# Tag_Tracker_v1.net
KiCad netlist of a schematic drawn in EAGLE
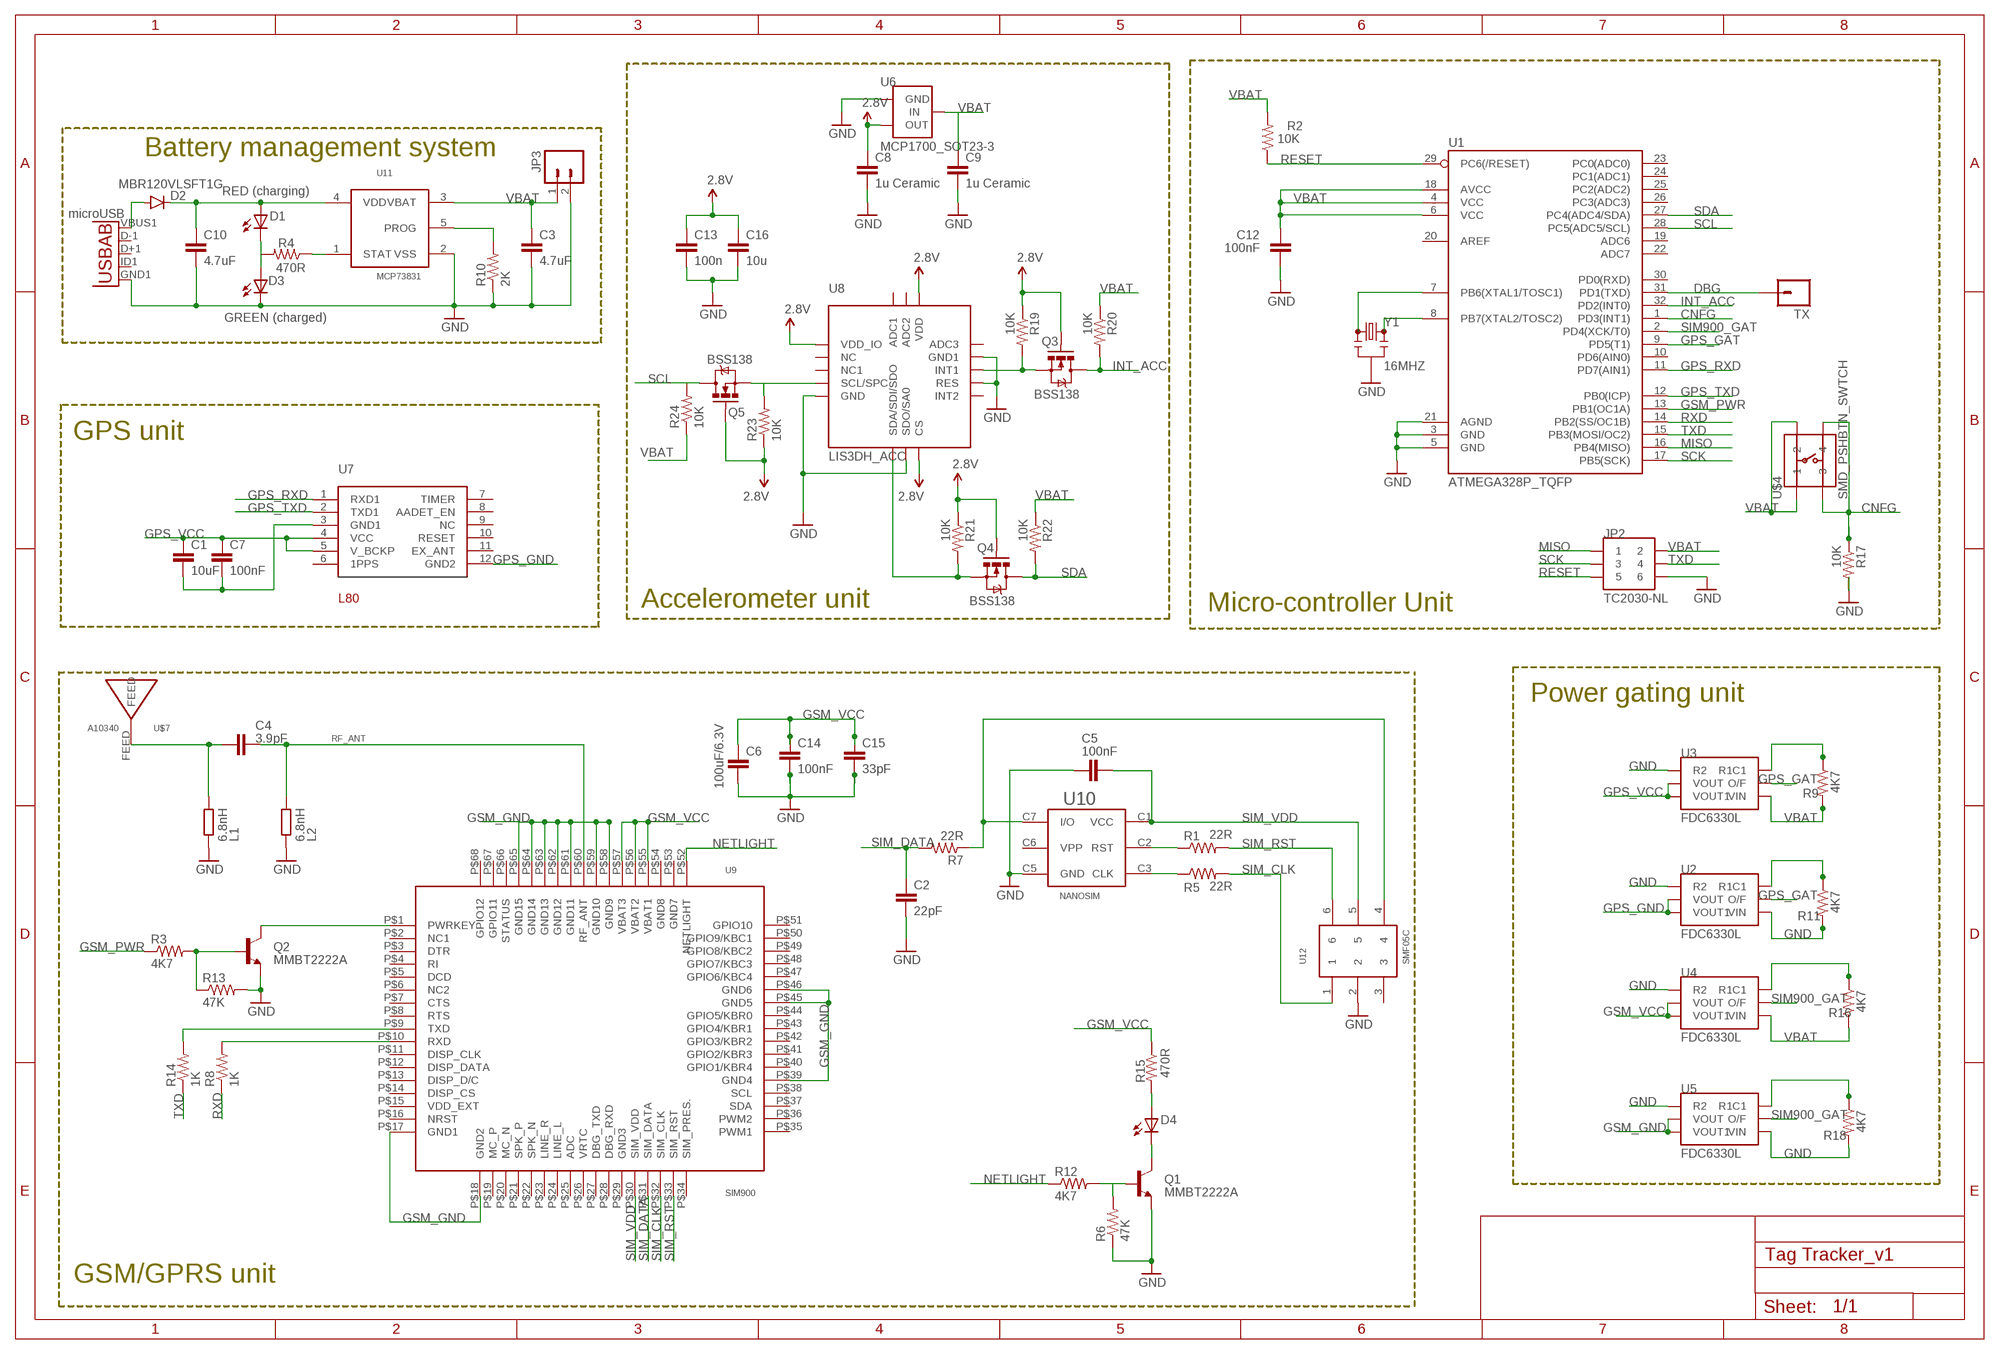
[diagram p0: schematic, sheet 1]

(export (version "E")
  (design (tool "Eeschema 10.0.6"))
  (components
    (comp (ref "C1")
      (value "10uF")
      (footprint "eagle-import:0603-CAP")
      (libsource (lib "eagle-import") (part "CAP0603-CAP"))
    )
    (comp (ref "C2")
      (value "22pF")
      (footprint "eagle-import:0603-CAP")
      (libsource (lib "eagle-import") (part "CAP0603-CAP"))
    )
    (comp (ref "C3")
      (value "4.7uF")
      (footprint "eagle-import:0603-CAP")
      (libsource (lib "eagle-import") (part "CAP0603-CAP"))
    )
    (comp (ref "C4")
      (value "3.9pF")
      (footprint "eagle-import:C0603-ROUND")
      (libsource (lib "eagle-import") (part "C-EU0603-RND"))
    )
    (comp (ref "C5")
      (value "100nF")
      (footprint "eagle-import:0603-CAP")
      (libsource (lib "eagle-import") (part "CAP0603-CAP"))
    )
    (comp (ref "C6")
      (value "100uF/6.3V")
      (footprint "eagle-import:1206")
      (libsource (lib "eagle-import") (part "CAP1206"))
    )
    (comp (ref "C7")
      (value "100nF")
      (footprint "eagle-import:0603-CAP")
      (libsource (lib "eagle-import") (part "CAP0603-CAP"))
    )
    (comp (ref "C8")
      (value "1u Ceramic")
      (footprint "eagle-import:0603-CAP")
      (libsource (lib "eagle-import") (part "0.1UF-100V-10%(0603)"))
    )
    (comp (ref "C9")
      (value "1u Ceramic")
      (footprint "eagle-import:0603-CAP")
      (libsource (lib "eagle-import") (part "0.1UF-100V-10%(0603)"))
    )
    (comp (ref "C10")
      (value "4.7uF")
      (footprint "eagle-import:0603-CAP")
      (libsource (lib "eagle-import") (part "CAP0603-CAP"))
    )
    (comp (ref "C12")
      (value "100nF")
      (footprint "eagle-import:0603-CAP")
      (libsource (lib "eagle-import") (part "CAP0603-CAP"))
    )
    (comp (ref "C13")
      (value "100n")
      (footprint "eagle-import:0603-CAP")
      (libsource (lib "eagle-import") (part "0.1UF-100V-10%(0603)"))
    )
    (comp (ref "C14")
      (value "100nF")
      (footprint "eagle-import:0603-CAP")
      (libsource (lib "eagle-import") (part "CAP0603-CAP"))
    )
    (comp (ref "C15")
      (value "33pF")
      (footprint "eagle-import:0603-CAP")
      (libsource (lib "eagle-import") (part "CAP0603-CAP"))
    )
    (comp (ref "C16")
      (value "10u")
      (footprint "eagle-import:0603-CAP")
      (libsource (lib "eagle-import") (part "0.1UF-100V-10%(0603)"))
    )
    (comp (ref "D1")
      (value "RED (charging)")
      (footprint "eagle-import:SML0603")
      (libsource (lib "eagle-import") (part "LEDSML0603"))
    )
    (comp (ref "D2")
      (value "MBR120VLSFT1G")
      (footprint "eagle-import:SOD-123")
      (libsource (lib "eagle-import") (part "DIODESOD123"))
    )
    (comp (ref "D3")
      (value "GREEN (charged)")
      (footprint "eagle-import:SML0603")
      (libsource (lib "eagle-import") (part "LEDSML0603"))
    )
    (comp (ref "D4")
      (value "LEDSML0603")
      (footprint "eagle-import:SML0603")
      (libsource (lib "eagle-import") (part "LEDSML0603"))
    )
    (comp (ref "JP2")
      (value "TC2030-NL")
      (footprint "eagle-import:TC2030-NL")
      (libsource (lib "eagle-import") (part "TC2030-NL"))
    )
    (comp (ref "JP3")
      (value "M02PTH")
      (footprint "eagle-import:1X02")
      (libsource (lib "eagle-import") (part "M02PTH"))
    )
    (comp (ref "L1")
      (value "6.8nH")
      (footprint "eagle-import:R0603-ROUND")
      (libsource (lib "eagle-import") (part "R-EU_0603-RND"))
    )
    (comp (ref "L2")
      (value "6.8nH")
      (footprint "eagle-import:R0603-ROUND")
      (libsource (lib "eagle-import") (part "R-EU_0603-RND"))
    )
    (comp (ref "MICRO_USB")
      (value "Micro USB")
      (footprint "eagle-import:USB-AB-MICRO-SMD_V03")
      (libsource (lib "eagle-import") (part "USB-ABCONN-11794"))
    )
    (comp (ref "Q1")
      (value "MMBT2222A")
      (footprint "eagle-import:SOT23-3")
      (libsource (lib "eagle-import") (part "TRANSISTOR_NPNMMBT2222A"))
    )
    (comp (ref "Q2")
      (value "MMBT2222A")
      (footprint "eagle-import:SOT23-3")
      (libsource (lib "eagle-import") (part "TRANSISTOR_NPNMMBT2222A"))
    )
    (comp (ref "Q3")
      (value "BSS138")
      (footprint "eagle-import:SOT23-3")
      (libsource (lib "eagle-import") (part "MOSFET-NCHANNELSMD"))
    )
    (comp (ref "Q4")
      (value "BSS138")
      (footprint "eagle-import:SOT23-3")
      (libsource (lib "eagle-import") (part "MOSFET-NCHANNELSMD"))
    )
    (comp (ref "Q5")
      (value "BSS138")
      (footprint "eagle-import:SOT23-3")
      (libsource (lib "eagle-import") (part "MOSFET-NCHANNELSMD"))
    )
    (comp (ref "R1")
      (value "22R")
      (footprint "eagle-import:0603-RES")
      (libsource (lib "eagle-import") (part "SparkFun-Resistors_RESISTOR0603-RES"))
    )
    (comp (ref "R2")
      (value "10K")
      (footprint "eagle-import:0603-RES")
      (libsource (lib "eagle-import") (part "SparkFun-Resistors_RESISTOR0603-RES"))
    )
    (comp (ref "R3")
      (value "4K7")
      (footprint "eagle-import:0603-RES")
      (libsource (lib "eagle-import") (part "SparkFun-Resistors_RESISTOR0603-RES"))
    )
    (comp (ref "R4")
      (value "470R")
      (footprint "eagle-import:0603-RES")
      (libsource (lib "eagle-import") (part "SparkFun-Resistors_RESISTOR0603-RES"))
    )
    (comp (ref "R5")
      (value "22R")
      (footprint "eagle-import:0603-RES")
      (libsource (lib "eagle-import") (part "SparkFun-Resistors_RESISTOR0603-RES"))
    )
    (comp (ref "R6")
      (value "47K")
      (footprint "eagle-import:0603-RES")
      (libsource (lib "eagle-import") (part "SparkFun-Resistors_RESISTOR0603-RES"))
    )
    (comp (ref "R7")
      (value "22R")
      (footprint "eagle-import:0603-RES")
      (libsource (lib "eagle-import") (part "SparkFun-Resistors_RESISTOR0603-RES"))
    )
    (comp (ref "R8")
      (value "1K")
      (footprint "eagle-import:0603-RES")
      (libsource (lib "eagle-import") (part "SparkFun-Resistors_RESISTOR0603-RES"))
    )
    (comp (ref "R9")
      (value "4K7")
      (footprint "eagle-import:0603-RES")
      (libsource (lib "eagle-import") (part "SparkFun-Resistors_RESISTOR0603-RES"))
    )
    (comp (ref "R10")
      (value "2K")
      (footprint "eagle-import:0603-RES")
      (libsource (lib "eagle-import") (part "SparkFun-Resistors_RESISTOR0603-RES"))
    )
    (comp (ref "R11")
      (value "4K7")
      (footprint "eagle-import:0603-RES")
      (libsource (lib "eagle-import") (part "SparkFun-Resistors_RESISTOR0603-RES"))
    )
    (comp (ref "R12")
      (value "4K7")
      (footprint "eagle-import:0603-RES")
      (libsource (lib "eagle-import") (part "SparkFun-Resistors_RESISTOR0603-RES"))
    )
    (comp (ref "R13")
      (value "47K")
      (footprint "eagle-import:0603-RES")
      (libsource (lib "eagle-import") (part "SparkFun-Resistors_RESISTOR0603-RES"))
    )
    (comp (ref "R14")
      (value "1K")
      (footprint "eagle-import:0603-RES")
      (libsource (lib "eagle-import") (part "SparkFun-Resistors_RESISTOR0603-RES"))
    )
    (comp (ref "R15")
      (value "470R")
      (footprint "eagle-import:0603-RES")
      (libsource (lib "eagle-import") (part "SparkFun-Resistors_RESISTOR0603-RES"))
    )
    (comp (ref "R16")
      (value "4K7")
      (footprint "eagle-import:0603-RES")
      (libsource (lib "eagle-import") (part "SparkFun-Resistors_RESISTOR0603-RES"))
    )
    (comp (ref "R17")
      (value "10K")
      (footprint "eagle-import:0603-RES")
      (libsource (lib "eagle-import") (part "SparkFun-Resistors_RESISTOR0603-RES"))
    )
    (comp (ref "R18")
      (value "4K7")
      (footprint "eagle-import:0603-RES")
      (libsource (lib "eagle-import") (part "SparkFun-Resistors_RESISTOR0603-RES"))
    )
    (comp (ref "R19")
      (value "10K")
      (footprint "eagle-import:0603-RES")
      (libsource (lib "eagle-import") (part "RESISTOR0603-RES"))
    )
    (comp (ref "R20")
      (value "10K")
      (footprint "eagle-import:0603-RES")
      (libsource (lib "eagle-import") (part "RESISTOR0603-RES"))
    )
    (comp (ref "R21")
      (value "10K")
      (footprint "eagle-import:0603-RES")
      (libsource (lib "eagle-import") (part "RESISTOR0603-RES"))
    )
    (comp (ref "R22")
      (value "10K")
      (footprint "eagle-import:0603-RES")
      (libsource (lib "eagle-import") (part "RESISTOR0603-RES"))
    )
    (comp (ref "R23")
      (value "10K")
      (footprint "eagle-import:0603-RES")
      (libsource (lib "eagle-import") (part "RESISTOR0603-RES"))
    )
    (comp (ref "R24")
      (value "10K")
      (footprint "eagle-import:0603-RES")
      (libsource (lib "eagle-import") (part "RESISTOR0603-RES"))
    )
    (comp (ref "TX")
      (value "M01PTH")
      (footprint "eagle-import:1X01")
      (libsource (lib "eagle-import") (part "M01PTH"))
    )
    (comp (ref "U$4")
      (value "SMD_PSHBTN_SWTCH")
      (footprint "eagle-import:KPT-1187B")
      (libsource (lib "eagle-import") (part "SMD_PSHBTN_SWTCH"))
    )
    (comp (ref "U$7")
      (value "A10340")
      (footprint "eagle-import:CALVUS_5BAND_SMD_A10340_0MM_EXCLUSION")
      (libsource (lib "eagle-import") (part "CALVUS_5BAND_SMD_A103400MM_EXCLUSION"))
    )
    (comp (ref "U1")
      (value "ATMEGA328P_TQFP")
      (footprint "eagle-import:TQFP32-08")
      (libsource (lib "eagle-import") (part "ATMEGA328P_TQFP"))
    )
    (comp (ref "U2")
      (value "FDC6330L")
      (footprint "eagle-import:FDC6330L")
      (libsource (lib "eagle-import") (part "FDC6330L"))
    )
    (comp (ref "U3")
      (value "FDC6330L")
      (footprint "eagle-import:FDC6330L")
      (libsource (lib "eagle-import") (part "FDC6330L"))
    )
    (comp (ref "U4")
      (value "FDC6330L")
      (footprint "eagle-import:FDC6330L")
      (libsource (lib "eagle-import") (part "FDC6330L"))
    )
    (comp (ref "U5")
      (value "FDC6330L")
      (footprint "eagle-import:FDC6330L")
      (libsource (lib "eagle-import") (part "FDC6330L"))
    )
    (comp (ref "U6")
      (value "MCP1700_SOT23-3")
      (footprint "eagle-import:MCP1700_SOT23-3")
      (libsource (lib "eagle-import") (part "MCP1700_SOT23-3"))
    )
    (comp (ref "U7")
      (value "L80")
      (footprint "eagle-import:L80")
      (libsource (lib "eagle-import") (part "L80"))
    )
    (comp (ref "U8")
      (value "LIS3DH_ACC")
      (footprint "eagle-import:LIS3DH_ACC")
      (libsource (lib "eagle-import") (part "LIS3DH_ACC"))
    )
    (comp (ref "U9")
      (value "SIM900")
      (footprint "eagle-import:SIM900")
      (libsource (lib "eagle-import") (part "SIM900"))
    )
    (comp (ref "U10")
      (value "NANOSIM")
      (footprint "eagle-import:NANOSIM")
      (libsource (lib "eagle-import") (part "NANOSIM"))
    )
    (comp (ref "U11")
      (value "MCP73831")
      (footprint "eagle-import:SOT23-5")
      (libsource (lib "eagle-import") (part "MCP73831"))
    )
    (comp (ref "U12")
      (value "SMF05C")
      (footprint "eagle-import:SC70-6")
      (libsource (lib "eagle-import") (part "SMF05C"))
    )
    (comp (ref "Y1")
      (value "16MHZ")
      (footprint "eagle-import:RESONATOR-SMD")
      (libsource (lib "eagle-import") (part "RESONATOR16MHZ"))
    )
  )
  (nets
    (net (code "1") (name "/CNFG") (class "Default")
      (node (ref "R17") (pin "1") (pinfunction "1_1") (pintype "passive"))
      (node (ref "U$4") (pin "P$3") (pinfunction "3_P$3") (pintype "bidirectional"))
      (node (ref "U$4") (pin "P$4") (pinfunction "4_P$4") (pintype "bidirectional"))
      (node (ref "U1") (pin "1") (pinfunction "PD3(INT1)_1") (pintype "bidirectional"))
    )
    (net (code "2") (name "/DBG") (class "Default")
      (node (ref "TX") (pin "1") (pinfunction "1_1") (pintype "passive"))
      (node (ref "U1") (pin "31") (pinfunction "PD1(TXD)_31") (pintype "bidirectional"))
    )
    (net (code "3") (name "/GPS_GAT") (class "Default")
      (node (ref "U1") (pin "9") (pinfunction "PD5(T1)_9") (pintype "bidirectional"))
      (node (ref "U2") (pin "P$5") (pinfunction "O/F_P$5") (pintype "bidirectional"))
      (node (ref "U3") (pin "P$5") (pinfunction "O/F_P$5") (pintype "bidirectional"))
    )
    (net (code "4") (name "/GPS_GND") (class "Default")
      (node (ref "C1") (pin "2") (pinfunction "2_2") (pintype "passive"))
      (node (ref "C7") (pin "2") (pinfunction "2_2") (pintype "passive"))
      (node (ref "U2") (pin "P$2") (pinfunction "VOUT_P$2") (pintype "bidirectional"))
      (node (ref "U2") (pin "P$3") (pinfunction "VOUT1_P$3") (pintype "bidirectional"))
      (node (ref "U7") (pin "12") (pinfunction "GND2_12") (pintype "power_in"))
      (node (ref "U7") (pin "3") (pinfunction "GND1_3") (pintype "power_in"))
    )
    (net (code "5") (name "/GPS_RXD") (class "Default")
      (node (ref "U1") (pin "11") (pinfunction "PD7(AIN1)_11") (pintype "bidirectional"))
      (node (ref "U7") (pin "1") (pinfunction "RXD1_1") (pintype "bidirectional"))
    )
    (net (code "6") (name "/GPS_TXD") (class "Default")
      (node (ref "U1") (pin "12") (pinfunction "PB0(ICP)_12") (pintype "bidirectional"))
      (node (ref "U7") (pin "2") (pinfunction "TXD1_2") (pintype "bidirectional"))
    )
    (net (code "7") (name "/GPS_VCC") (class "Default")
      (node (ref "C1") (pin "1") (pinfunction "1_1") (pintype "passive"))
      (node (ref "C7") (pin "1") (pinfunction "1_1") (pintype "passive"))
      (node (ref "U3") (pin "P$2") (pinfunction "VOUT_P$2") (pintype "bidirectional"))
      (node (ref "U3") (pin "P$3") (pinfunction "VOUT1_P$3") (pintype "bidirectional"))
      (node (ref "U7") (pin "4") (pinfunction "VCC_4") (pintype "power_in"))
      (node (ref "U7") (pin "5") (pinfunction "V_BCKP_5") (pintype "power_in"))
    )
    (net (code "8") (name "/GSM_GND") (class "Default")
      (node (ref "U5") (pin "P$2") (pinfunction "VOUT_P$2") (pintype "bidirectional"))
      (node (ref "U5") (pin "P$3") (pinfunction "VOUT1_P$3") (pintype "bidirectional"))
      (node (ref "U9") (pin "P$17") (pinfunction "GND1_P$17") (pintype "bidirectional"))
      (node (ref "U9") (pin "P$18") (pinfunction "GND2_P$18") (pintype "bidirectional"))
      (node (ref "U9") (pin "P$39") (pinfunction "GND4_P$39") (pintype "bidirectional"))
      (node (ref "U9") (pin "P$45") (pinfunction "GND5_P$45") (pintype "bidirectional"))
      (node (ref "U9") (pin "P$46") (pinfunction "GND6_P$46") (pintype "bidirectional"))
      (node (ref "U9") (pin "P$58") (pinfunction "GND9_P$58") (pintype "bidirectional"))
      (node (ref "U9") (pin "P$59") (pinfunction "GND10_P$59") (pintype "bidirectional"))
      (node (ref "U9") (pin "P$61") (pinfunction "GND11_P$61") (pintype "bidirectional"))
      (node (ref "U9") (pin "P$62") (pinfunction "GND12_P$62") (pintype "bidirectional"))
      (node (ref "U9") (pin "P$63") (pinfunction "GND13_P$63") (pintype "bidirectional"))
      (node (ref "U9") (pin "P$64") (pinfunction "GND14_P$64") (pintype "bidirectional"))
      (node (ref "U9") (pin "P$65") (pinfunction "GND15_P$65") (pintype "bidirectional"))
    )
    (net (code "9") (name "/GSM_PWR") (class "Default")
      (node (ref "R3") (pin "1") (pinfunction "1_1") (pintype "passive"))
      (node (ref "U1") (pin "13") (pinfunction "PB1(OC1A)_13") (pintype "bidirectional"))
    )
    (net (code "10") (name "/GSM_VCC") (class "Default")
      (node (ref "C14") (pin "1") (pinfunction "1_1") (pintype "passive"))
      (node (ref "C15") (pin "1") (pinfunction "1_1") (pintype "passive"))
      (node (ref "C6") (pin "1") (pinfunction "1_1") (pintype "passive"))
      (node (ref "R15") (pin "1") (pinfunction "1_1") (pintype "passive"))
      (node (ref "U4") (pin "P$2") (pinfunction "VOUT_P$2") (pintype "bidirectional"))
      (node (ref "U4") (pin "P$3") (pinfunction "VOUT1_P$3") (pintype "bidirectional"))
      (node (ref "U9") (pin "P$55") (pinfunction "VBAT1_P$55") (pintype "bidirectional"))
      (node (ref "U9") (pin "P$56") (pinfunction "VBAT2_P$56") (pintype "bidirectional"))
      (node (ref "U9") (pin "P$57") (pinfunction "VBAT3_P$57") (pintype "bidirectional"))
    )
    (net (code "11") (name "/INT_ACC") (class "Default")
      (node (ref "Q3") (pin "3") (pinfunction "D_3") (pintype "passive"))
      (node (ref "R20") (pin "2") (pinfunction "2_2") (pintype "passive"))
      (node (ref "U1") (pin "32") (pinfunction "PD2(INT0)_32") (pintype "bidirectional"))
    )
    (net (code "12") (name "/MISO") (class "Default")
      (node (ref "JP2") (pin "P$1") (pinfunction "1_P$1") (pintype "bidirectional"))
      (node (ref "U1") (pin "16") (pinfunction "PB4(MISO)_16") (pintype "bidirectional"))
    )
    (net (code "13") (name "/NETLIGHT") (class "Default")
      (node (ref "R12") (pin "1") (pinfunction "1_1") (pintype "passive"))
      (node (ref "U9") (pin "P$52") (pinfunction "NETLIGHT_P$52") (pintype "bidirectional"))
    )
    (net (code "14") (name "/RESET") (class "Default")
      (node (ref "JP2") (pin "P$5") (pinfunction "5_P$5") (pintype "bidirectional"))
      (node (ref "R2") (pin "1") (pinfunction "1_1") (pintype "passive"))
      (node (ref "U1") (pin "29") (pinfunction "PC6(/RESET)_29") (pintype "bidirectional"))
    )
    (net (code "15") (name "/RXD") (class "Default")
      (node (ref "R8") (pin "1") (pinfunction "1_1") (pintype "passive"))
      (node (ref "U1") (pin "14") (pinfunction "PB2(SS/OC1B)_14") (pintype "bidirectional"))
    )
    (net (code "16") (name "/SCK") (class "Default")
      (node (ref "JP2") (pin "P$3") (pinfunction "3_P$3") (pintype "bidirectional"))
      (node (ref "U1") (pin "17") (pinfunction "PB5(SCK)_17") (pintype "bidirectional"))
    )
    (net (code "17") (name "/SCL") (class "Default")
      (node (ref "Q5") (pin "3") (pinfunction "D_3") (pintype "passive"))
      (node (ref "R24") (pin "2") (pinfunction "2_2") (pintype "passive"))
      (node (ref "U1") (pin "28") (pinfunction "PC5(ADC5/SCL)_28") (pintype "bidirectional"))
    )
    (net (code "18") (name "/SDA") (class "Default")
      (node (ref "Q4") (pin "3") (pinfunction "D_3") (pintype "passive"))
      (node (ref "R22") (pin "2") (pinfunction "2_2") (pintype "passive"))
      (node (ref "U1") (pin "27") (pinfunction "PC4(ADC4/SDA)_27") (pintype "bidirectional"))
    )
    (net (code "19") (name "/SIM900_GAT") (class "Default")
      (node (ref "U1") (pin "2") (pinfunction "PD4(XCK/T0)_2") (pintype "bidirectional"))
      (node (ref "U4") (pin "P$5") (pinfunction "O/F_P$5") (pintype "bidirectional"))
      (node (ref "U5") (pin "P$5") (pinfunction "O/F_P$5") (pintype "bidirectional"))
    )
    (net (code "20") (name "/SIM_CLK") (class "Default")
      (node (ref "R5") (pin "2") (pinfunction "2_2") (pintype "passive"))
      (node (ref "U12") (pin "1") (pinfunction "1_1") (pintype "bidirectional"))
      (node (ref "U9") (pin "P$32") (pinfunction "SIM_CLK_P$32") (pintype "bidirectional"))
    )
    (net (code "21") (name "/SIM_DATA") (class "Default")
      (node (ref "C2") (pin "1") (pinfunction "1_1") (pintype "passive"))
      (node (ref "R7") (pin "2") (pinfunction "2_2") (pintype "passive"))
      (node (ref "U9") (pin "P$31") (pinfunction "SIM_DATA_P$31") (pintype "bidirectional"))
    )
    (net (code "22") (name "/SIM_RST") (class "Default")
      (node (ref "R1") (pin "2") (pinfunction "2_2") (pintype "passive"))
      (node (ref "U12") (pin "6") (pinfunction "6_6") (pintype "bidirectional"))
      (node (ref "U9") (pin "P$33") (pinfunction "SIM_RST_P$33") (pintype "bidirectional"))
    )
    (net (code "23") (name "/SIM_VDD") (class "Default")
      (node (ref "C5") (pin "1") (pinfunction "1_1") (pintype "passive"))
      (node (ref "U10") (pin "C1") (pinfunction "VCC_C1") (pintype "bidirectional"))
      (node (ref "U12") (pin "5") (pinfunction "5_5") (pintype "bidirectional"))
      (node (ref "U9") (pin "P$30") (pinfunction "SIM_VDD_P$30") (pintype "bidirectional"))
    )
    (net (code "24") (name "/TXD") (class "Default")
      (node (ref "JP2") (pin "P$4") (pinfunction "4_P$4") (pintype "bidirectional"))
      (node (ref "R14") (pin "1") (pinfunction "1_1") (pintype "passive"))
      (node (ref "U1") (pin "15") (pinfunction "PB3(MOSI/OC2)_15") (pintype "bidirectional"))
    )
    (net (code "25") (name "/VBAT") (class "Default")
      (node (ref "C12") (pin "1") (pinfunction "1_1") (pintype "passive"))
      (node (ref "C3") (pin "1") (pinfunction "1_1") (pintype "passive"))
      (node (ref "C9") (pin "1") (pinfunction "1_1") (pintype "passive"))
      (node (ref "JP2") (pin "P$2") (pinfunction "2_P$2") (pintype "bidirectional"))
      (node (ref "JP3") (pin "1") (pinfunction "1_1") (pintype "passive"))
      (node (ref "R16") (pin "2") (pinfunction "2_2") (pintype "passive"))
      (node (ref "R2") (pin "2") (pinfunction "2_2") (pintype "passive"))
      (node (ref "R20") (pin "1") (pinfunction "1_1") (pintype "passive"))
      (node (ref "R22") (pin "1") (pinfunction "1_1") (pintype "passive"))
      (node (ref "R24") (pin "1") (pinfunction "1_1") (pintype "passive"))
      (node (ref "R9") (pin "2") (pinfunction "2_2") (pintype "passive"))
      (node (ref "U$4") (pin "P$1") (pinfunction "1_P$1") (pintype "bidirectional"))
      (node (ref "U$4") (pin "P$2") (pinfunction "2_P$2") (pintype "bidirectional"))
      (node (ref "U1") (pin "18") (pinfunction "AVCC_18") (pintype "bidirectional"))
      (node (ref "U1") (pin "4") (pinfunction "VCC_4") (pintype "bidirectional"))
      (node (ref "U1") (pin "6") (pinfunction "VCC_6") (pintype "bidirectional"))
      (node (ref "U11") (pin "3") (pinfunction "VBAT_3") (pintype "bidirectional"))
      (node (ref "U3") (pin "P$4") (pinfunction "VIN_P$4") (pintype "bidirectional"))
      (node (ref "U4") (pin "P$4") (pinfunction "VIN_P$4") (pintype "bidirectional"))
      (node (ref "U6") (pin "P$3") (pinfunction "IN_P$3") (pintype "bidirectional"))
    )
    (net (code "26") (name "2.8V") (class "Default")
      (node (ref "C13") (pin "1") (pinfunction "1_1") (pintype "passive"))
      (node (ref "C16") (pin "1") (pinfunction "1_1") (pintype "passive"))
      (node (ref "C8") (pin "1") (pinfunction "1_1") (pintype "passive"))
      (node (ref "Q3") (pin "1") (pinfunction "G_1") (pintype "passive"))
      (node (ref "Q4") (pin "1") (pinfunction "G_1") (pintype "passive"))
      (node (ref "Q5") (pin "1") (pinfunction "G_1") (pintype "passive"))
      (node (ref "R19") (pin "1") (pinfunction "1_1") (pintype "passive"))
      (node (ref "R21") (pin "1") (pinfunction "1_1") (pintype "passive"))
      (node (ref "R23") (pin "1") (pinfunction "1_1") (pintype "passive"))
      (node (ref "U6") (pin "P$2") (pinfunction "OUT_P$2") (pintype "bidirectional"))
      (node (ref "U8") (pin "P$1") (pinfunction "VDD_IO_P$1") (pintype "bidirectional"))
      (node (ref "U8") (pin "P$14") (pinfunction "VDD_P$14") (pintype "bidirectional"))
      (node (ref "U8") (pin "P$8") (pinfunction "CS_P$8") (pintype "bidirectional"))
    )
    (net (code "27") (name "GND") (class "Default")
      (node (ref "C10") (pin "2") (pinfunction "2_2") (pintype "passive"))
      (node (ref "C12") (pin "2") (pinfunction "2_2") (pintype "passive"))
      (node (ref "C13") (pin "2") (pinfunction "2_2") (pintype "passive"))
      (node (ref "C14") (pin "2") (pinfunction "2_2") (pintype "passive"))
      (node (ref "C15") (pin "2") (pinfunction "2_2") (pintype "passive"))
      (node (ref "C16") (pin "2") (pinfunction "2_2") (pintype "passive"))
      (node (ref "C2") (pin "2") (pinfunction "2_2") (pintype "passive"))
      (node (ref "C3") (pin "2") (pinfunction "2_2") (pintype "passive"))
      (node (ref "C5") (pin "2") (pinfunction "2_2") (pintype "passive"))
      (node (ref "C6") (pin "2") (pinfunction "2_2") (pintype "passive"))
      (node (ref "C8") (pin "2") (pinfunction "2_2") (pintype "passive"))
      (node (ref "C9") (pin "2") (pinfunction "2_2") (pintype "passive"))
      (node (ref "D3") (pin "C") (pinfunction "C_C") (pintype "passive"))
      (node (ref "JP2") (pin "P$6") (pinfunction "6_P$6") (pintype "bidirectional"))
      (node (ref "JP3") (pin "2") (pinfunction "2_2") (pintype "passive"))
      (node (ref "L1") (pin "1") (pinfunction "1_1") (pintype "passive"))
      (node (ref "L2") (pin "1") (pinfunction "1_1") (pintype "passive"))
      (node (ref "MICRO_USB") (pin "GND1") (pinfunction "GND_GND1") (pintype "bidirectional"))
      (node (ref "Q1") (pin "2") (pinfunction "E_2") (pintype "passive"))
      (node (ref "Q2") (pin "2") (pinfunction "E_2") (pintype "passive"))
      (node (ref "R10") (pin "1") (pinfunction "1_1") (pintype "passive"))
      (node (ref "R11") (pin "2") (pinfunction "2_2") (pintype "passive"))
      (node (ref "R13") (pin "2") (pinfunction "2_2") (pintype "passive"))
      (node (ref "R17") (pin "2") (pinfunction "2_2") (pintype "passive"))
      (node (ref "R18") (pin "2") (pinfunction "2_2") (pintype "passive"))
      (node (ref "R6") (pin "1") (pinfunction "1_1") (pintype "passive"))
      (node (ref "U1") (pin "21") (pinfunction "AGND_21") (pintype "bidirectional"))
      (node (ref "U1") (pin "3") (pinfunction "GND_3") (pintype "bidirectional"))
      (node (ref "U1") (pin "5") (pinfunction "GND_5") (pintype "bidirectional"))
      (node (ref "U10") (pin "C5") (pinfunction "GND_C5") (pintype "bidirectional"))
      (node (ref "U11") (pin "2") (pinfunction "VSS_2") (pintype "bidirectional"))
      (node (ref "U12") (pin "2") (pinfunction "2_2") (pintype "bidirectional"))
      (node (ref "U2") (pin "P$1") (pinfunction "R2_P$1") (pintype "bidirectional"))
      (node (ref "U2") (pin "P$4") (pinfunction "VIN_P$4") (pintype "bidirectional"))
      (node (ref "U3") (pin "P$1") (pinfunction "R2_P$1") (pintype "bidirectional"))
      (node (ref "U4") (pin "P$1") (pinfunction "R2_P$1") (pintype "bidirectional"))
      (node (ref "U5") (pin "P$1") (pinfunction "R2_P$1") (pintype "bidirectional"))
      (node (ref "U5") (pin "P$4") (pinfunction "VIN_P$4") (pintype "bidirectional"))
      (node (ref "U6") (pin "P$1") (pinfunction "GND_P$1") (pintype "bidirectional"))
      (node (ref "U8") (pin "P$10") (pinfunction "RES_P$10") (pintype "bidirectional"))
      (node (ref "U8") (pin "P$12") (pinfunction "GND1_P$12") (pintype "bidirectional"))
      (node (ref "U8") (pin "P$5") (pinfunction "GND_P$5") (pintype "bidirectional"))
      (node (ref "U8") (pin "P$7") (pinfunction "SDO/SA0_P$7") (pintype "bidirectional"))
      (node (ref "Y1") (pin "2") (pinfunction "2_2") (pintype "passive"))
    )
    (net (code "28") (name "Net-(C4-Pad2)") (class "Default")
      (node (ref "C4") (pin "2") (pinfunction "2_2") (pintype "passive"))
      (node (ref "L1") (pin "2") (pinfunction "2_2") (pintype "passive"))
      (node (ref "U$7") (pin "FEED") (pinfunction "FEED_FEED") (pintype "bidirectional"))
    )
    (net (code "29") (name "Net-(D1-PadC)") (class "Default")
      (node (ref "D1") (pin "C") (pinfunction "C_C") (pintype "passive"))
      (node (ref "D3") (pin "A") (pinfunction "A_A") (pintype "passive"))
      (node (ref "R4") (pin "2") (pinfunction "2_2") (pintype "passive"))
    )
    (net (code "30") (name "Net-(D4-PadA)") (class "Default")
      (node (ref "D4") (pin "A") (pinfunction "A_A") (pintype "passive"))
      (node (ref "R15") (pin "2") (pinfunction "2_2") (pintype "passive"))
    )
    (net (code "31") (name "Net-(MICRO_USB-VBUS)") (class "Default")
      (node (ref "D2") (pin "A") (pinfunction "A_A") (pintype "passive"))
      (node (ref "MICRO_USB") (pin "VBUS1") (pinfunction "VBUS_VBUS1") (pintype "bidirectional"))
    )
    (net (code "32") (name "Net-(Q1-B)") (class "Default")
      (node (ref "Q1") (pin "1") (pinfunction "B_1") (pintype "passive"))
      (node (ref "R12") (pin "2") (pinfunction "2_2") (pintype "passive"))
      (node (ref "R6") (pin "2") (pinfunction "2_2") (pintype "passive"))
    )
    (net (code "33") (name "Net-(Q1-C)") (class "Default")
      (node (ref "D4") (pin "C") (pinfunction "C_C") (pintype "passive"))
      (node (ref "Q1") (pin "3") (pinfunction "C_3") (pintype "passive"))
    )
    (net (code "34") (name "Net-(Q2-B)") (class "Default")
      (node (ref "Q2") (pin "1") (pinfunction "B_1") (pintype "passive"))
      (node (ref "R13") (pin "1") (pinfunction "1_1") (pintype "passive"))
      (node (ref "R3") (pin "2") (pinfunction "2_2") (pintype "passive"))
    )
    (net (code "35") (name "Net-(Q2-C)") (class "Default")
      (node (ref "Q2") (pin "3") (pinfunction "C_3") (pintype "passive"))
      (node (ref "U9") (pin "P$1") (pinfunction "PWRKEY_P$1") (pintype "bidirectional"))
    )
    (net (code "36") (name "Net-(Q3-S)") (class "Default")
      (node (ref "Q3") (pin "2") (pinfunction "S_2") (pintype "passive"))
      (node (ref "R19") (pin "2") (pinfunction "2_2") (pintype "passive"))
      (node (ref "U8") (pin "P$11") (pinfunction "INT1_P$11") (pintype "bidirectional"))
    )
    (net (code "37") (name "Net-(Q4-S)") (class "Default")
      (node (ref "Q4") (pin "2") (pinfunction "S_2") (pintype "passive"))
      (node (ref "R21") (pin "2") (pinfunction "2_2") (pintype "passive"))
      (node (ref "U8") (pin "P$6") (pinfunction "SDA/SDI/SDO_P$6") (pintype "bidirectional"))
    )
    (net (code "38") (name "Net-(Q5-S)") (class "Default")
      (node (ref "Q5") (pin "2") (pinfunction "S_2") (pintype "passive"))
      (node (ref "R23") (pin "2") (pinfunction "2_2") (pintype "passive"))
      (node (ref "U8") (pin "P$4") (pinfunction "SCL/SPC_P$4") (pintype "bidirectional"))
    )
    (net (code "39") (name "Net-(U1-PB6(XTAL1{slash}TOSC1))") (class "Default")
      (node (ref "U1") (pin "7") (pinfunction "PB6(XTAL1/TOSC1)_7") (pintype "bidirectional"))
      (node (ref "Y1") (pin "1") (pinfunction "1_1") (pintype "passive"))
    )
    (net (code "40") (name "Net-(U1-PB7(XTAL2{slash}TOSC2))") (class "Default")
      (node (ref "U1") (pin "8") (pinfunction "PB7(XTAL2/TOSC2)_8") (pintype "bidirectional"))
      (node (ref "Y1") (pin "3") (pinfunction "3_3") (pintype "passive"))
    )
    (net (code "41") (name "Net-(U2-R1C1)") (class "Default")
      (node (ref "R11") (pin "1") (pinfunction "1_1") (pintype "passive"))
      (node (ref "U2") (pin "P$6") (pinfunction "R1C1_P$6") (pintype "bidirectional"))
    )
    (net (code "42") (name "Net-(U3-R1C1)") (class "Default")
      (node (ref "R9") (pin "1") (pinfunction "1_1") (pintype "passive"))
      (node (ref "U3") (pin "P$6") (pinfunction "R1C1_P$6") (pintype "bidirectional"))
    )
    (net (code "43") (name "Net-(U4-R1C1)") (class "Default")
      (node (ref "R16") (pin "1") (pinfunction "1_1") (pintype "passive"))
      (node (ref "U4") (pin "P$6") (pinfunction "R1C1_P$6") (pintype "bidirectional"))
    )
    (net (code "44") (name "Net-(U5-R1C1)") (class "Default")
      (node (ref "R18") (pin "1") (pinfunction "1_1") (pintype "passive"))
      (node (ref "U5") (pin "P$6") (pinfunction "R1C1_P$6") (pintype "bidirectional"))
    )
    (net (code "45") (name "Net-(U9-RF_ANT)") (class "Default")
      (node (ref "C4") (pin "1") (pinfunction "1_1") (pintype "passive"))
      (node (ref "L2") (pin "2") (pinfunction "2_2") (pintype "passive"))
      (node (ref "U9") (pin "P$60") (pinfunction "RF_ANT_P$60") (pintype "bidirectional"))
    )
    (net (code "46") (name "Net-(U9-RXD)") (class "Default")
      (node (ref "R8") (pin "2") (pinfunction "2_2") (pintype "passive"))
      (node (ref "U9") (pin "P$10") (pinfunction "RXD_P$10") (pintype "bidirectional"))
    )
    (net (code "47") (name "Net-(U9-TXD)") (class "Default")
      (node (ref "R14") (pin "2") (pinfunction "2_2") (pintype "passive"))
      (node (ref "U9") (pin "P$9") (pinfunction "TXD_P$9") (pintype "bidirectional"))
    )
    (net (code "48") (name "Net-(U10-CLK)") (class "Default")
      (node (ref "R5") (pin "1") (pinfunction "1_1") (pintype "passive"))
      (node (ref "U10") (pin "C3") (pinfunction "CLK_C3") (pintype "bidirectional"))
    )
    (net (code "49") (name "Net-(U10-I{slash}O)") (class "Default")
      (node (ref "R7") (pin "1") (pinfunction "1_1") (pintype "passive"))
      (node (ref "U10") (pin "C7") (pinfunction "I/O_C7") (pintype "bidirectional"))
      (node (ref "U12") (pin "4") (pinfunction "4_4") (pintype "bidirectional"))
    )
    (net (code "50") (name "Net-(U10-RST)") (class "Default")
      (node (ref "R1") (pin "1") (pinfunction "1_1") (pintype "passive"))
      (node (ref "U10") (pin "C2") (pinfunction "RST_C2") (pintype "bidirectional"))
    )
    (net (code "51") (name "Net-(U11-PROG)") (class "Default")
      (node (ref "R10") (pin "2") (pinfunction "2_2") (pintype "passive"))
      (node (ref "U11") (pin "5") (pinfunction "PROG_5") (pintype "bidirectional"))
    )
    (net (code "52") (name "Net-(U11-STAT)") (class "Default")
      (node (ref "R4") (pin "1") (pinfunction "1_1") (pintype "passive"))
      (node (ref "U11") (pin "1") (pinfunction "STAT_1") (pintype "bidirectional"))
    )
    (net (code "53") (name "Net-(U11-VDD)") (class "Default")
      (node (ref "C10") (pin "1") (pinfunction "1_1") (pintype "passive"))
      (node (ref "D1") (pin "A") (pinfunction "A_A") (pintype "passive"))
      (node (ref "D2") (pin "C") (pinfunction "C_C") (pintype "passive"))
      (node (ref "U11") (pin "4") (pinfunction "VDD_4") (pintype "bidirectional"))
    )
    (net (code "54") (name "unconnected-(MICRO_USB-D+-PadD+1)") (class "Default")
      (node (ref "MICRO_USB") (pin "D+1") (pinfunction "D+_D+1") (pintype "bidirectional"))
    )
    (net (code "55") (name "unconnected-(MICRO_USB-D--PadD-1)") (class "Default")
      (node (ref "MICRO_USB") (pin "D-1") (pinfunction "D-_D-1") (pintype "bidirectional"))
    )
    (net (code "56") (name "unconnected-(MICRO_USB-USBID-PadID1)") (class "Default")
      (node (ref "MICRO_USB") (pin "ID1") (pinfunction "USBID_ID1") (pintype "bidirectional"))
    )
    (net (code "57") (name "unconnected-(U1-ADC6-Pad19)") (class "Default")
      (node (ref "U1") (pin "19") (pinfunction "ADC6_19") (pintype "bidirectional"))
    )
    (net (code "58") (name "unconnected-(U1-ADC7-Pad22)") (class "Default")
      (node (ref "U1") (pin "22") (pinfunction "ADC7_22") (pintype "bidirectional"))
    )
    (net (code "59") (name "unconnected-(U1-AREF-Pad20)") (class "Default")
      (node (ref "U1") (pin "20") (pinfunction "AREF_20") (pintype "bidirectional"))
    )
    (net (code "60") (name "unconnected-(U1-PC0(ADC0)-Pad23)") (class "Default")
      (node (ref "U1") (pin "23") (pinfunction "PC0(ADC0)_23") (pintype "bidirectional"))
    )
    (net (code "61") (name "unconnected-(U1-PC1(ADC1)-Pad24)") (class "Default")
      (node (ref "U1") (pin "24") (pinfunction "PC1(ADC1)_24") (pintype "bidirectional"))
    )
    (net (code "62") (name "unconnected-(U1-PC2(ADC2)-Pad25)") (class "Default")
      (node (ref "U1") (pin "25") (pinfunction "PC2(ADC2)_25") (pintype "bidirectional"))
    )
    (net (code "63") (name "unconnected-(U1-PC3(ADC3)-Pad26)") (class "Default")
      (node (ref "U1") (pin "26") (pinfunction "PC3(ADC3)_26") (pintype "bidirectional"))
    )
    (net (code "64") (name "unconnected-(U1-PD0(RXD)-Pad30)") (class "Default")
      (node (ref "U1") (pin "30") (pinfunction "PD0(RXD)_30") (pintype "bidirectional"))
    )
    (net (code "65") (name "unconnected-(U1-PD6(AIN0)-Pad10)") (class "Default")
      (node (ref "U1") (pin "10") (pinfunction "PD6(AIN0)_10") (pintype "bidirectional"))
    )
    (net (code "66") (name "unconnected-(U7-1PPS-Pad6)") (class "Default")
      (node (ref "U7") (pin "6") (pinfunction "1PPS_6") (pintype "bidirectional"))
    )
    (net (code "67") (name "unconnected-(U7-AADET_EN-Pad8)") (class "Default")
      (node (ref "U7") (pin "8") (pinfunction "AADET_EN_8") (pintype "bidirectional"))
    )
    (net (code "68") (name "unconnected-(U7-EX_ANT-Pad11)") (class "Default")
      (node (ref "U7") (pin "11") (pinfunction "EX_ANT_11") (pintype "bidirectional"))
    )
    (net (code "69") (name "unconnected-(U7-NC-Pad9)") (class "Default")
      (node (ref "U7") (pin "9") (pinfunction "NC_9") (pintype "bidirectional"))
    )
    (net (code "70") (name "unconnected-(U7-RESET-Pad10)") (class "Default")
      (node (ref "U7") (pin "10") (pinfunction "RESET_10") (pintype "bidirectional"))
    )
    (net (code "71") (name "unconnected-(U7-TIMER-Pad7)") (class "Default")
      (node (ref "U7") (pin "7") (pinfunction "TIMER_7") (pintype "bidirectional"))
    )
    (net (code "72") (name "unconnected-(U8-ADC1-PadP$16)") (class "Default")
      (node (ref "U8") (pin "P$16") (pinfunction "ADC1_P$16") (pintype "bidirectional"))
    )
    (net (code "73") (name "unconnected-(U8-ADC2-PadP$15)") (class "Default")
      (node (ref "U8") (pin "P$15") (pinfunction "ADC2_P$15") (pintype "bidirectional"))
    )
    (net (code "74") (name "unconnected-(U8-ADC3-PadP$13)") (class "Default")
      (node (ref "U8") (pin "P$13") (pinfunction "ADC3_P$13") (pintype "bidirectional"))
    )
    (net (code "75") (name "unconnected-(U8-INT2-PadP$9)") (class "Default")
      (node (ref "U8") (pin "P$9") (pinfunction "INT2_P$9") (pintype "bidirectional"))
    )
    (net (code "76") (name "unconnected-(U8-NC-PadP$2)") (class "Default")
      (node (ref "U8") (pin "P$2") (pinfunction "NC_P$2") (pintype "bidirectional"))
    )
    (net (code "77") (name "unconnected-(U8-NC1-PadP$3)") (class "Default")
      (node (ref "U8") (pin "P$3") (pinfunction "NC1_P$3") (pintype "bidirectional"))
    )
    (net (code "78") (name "unconnected-(U9-ADC-PadP$25)") (class "Default")
      (node (ref "U9") (pin "P$25") (pinfunction "ADC_P$25") (pintype "bidirectional"))
    )
    (net (code "79") (name "unconnected-(U9-CTS-PadP$7)") (class "Default")
      (node (ref "U9") (pin "P$7") (pinfunction "CTS_P$7") (pintype "bidirectional"))
    )
    (net (code "80") (name "unconnected-(U9-DBG_RXD-PadP$28)") (class "Default")
      (node (ref "U9") (pin "P$28") (pinfunction "DBG_RXD_P$28") (pintype "bidirectional"))
    )
    (net (code "81") (name "unconnected-(U9-DBG_TXD-PadP$27)") (class "Default")
      (node (ref "U9") (pin "P$27") (pinfunction "DBG_TXD_P$27") (pintype "bidirectional"))
    )
    (net (code "82") (name "unconnected-(U9-DCD-PadP$5)") (class "Default")
      (node (ref "U9") (pin "P$5") (pinfunction "DCD_P$5") (pintype "bidirectional"))
    )
    (net (code "83") (name "unconnected-(U9-DISP_CLK-PadP$11)") (class "Default")
      (node (ref "U9") (pin "P$11") (pinfunction "DISP_CLK_P$11") (pintype "bidirectional"))
    )
    (net (code "84") (name "unconnected-(U9-DISP_CS-PadP$14)") (class "Default")
      (node (ref "U9") (pin "P$14") (pinfunction "DISP_CS_P$14") (pintype "bidirectional"))
    )
    (net (code "85") (name "unconnected-(U9-DISP_DATA-PadP$12)") (class "Default")
      (node (ref "U9") (pin "P$12") (pinfunction "DISP_DATA_P$12") (pintype "bidirectional"))
    )
    (net (code "86") (name "unconnected-(U9-DISP_D{slash}C-PadP$13)") (class "Default")
      (node (ref "U9") (pin "P$13") (pinfunction "DISP_D/C_P$13") (pintype "bidirectional"))
    )
    (net (code "87") (name "unconnected-(U9-DTR-PadP$3)") (class "Default")
      (node (ref "U9") (pin "P$3") (pinfunction "DTR_P$3") (pintype "bidirectional"))
    )
    (net (code "88") (name "unconnected-(U9-GND3-PadP$29)") (class "Default")
      (node (ref "U9") (pin "P$29") (pinfunction "GND3_P$29") (pintype "bidirectional"))
    )
    (net (code "89") (name "unconnected-(U9-GND7-PadP$53)") (class "Default")
      (node (ref "U9") (pin "P$53") (pinfunction "GND7_P$53") (pintype "bidirectional"))
    )
    (net (code "90") (name "unconnected-(U9-GND8-PadP$54)") (class "Default")
      (node (ref "U9") (pin "P$54") (pinfunction "GND8_P$54") (pintype "bidirectional"))
    )
    (net (code "91") (name "unconnected-(U9-GPIO1{slash}KBR4-PadP$40)") (class "Default")
      (node (ref "U9") (pin "P$40") (pinfunction "GPIO1/KBR4_P$40") (pintype "bidirectional"))
    )
    (net (code "92") (name "unconnected-(U9-GPIO2{slash}KBR3-PadP$41)") (class "Default")
      (node (ref "U9") (pin "P$41") (pinfunction "GPIO2/KBR3_P$41") (pintype "bidirectional"))
    )
    (net (code "93") (name "unconnected-(U9-GPIO3{slash}KBR2-PadP$42)") (class "Default")
      (node (ref "U9") (pin "P$42") (pinfunction "GPIO3/KBR2_P$42") (pintype "bidirectional"))
    )
    (net (code "94") (name "unconnected-(U9-GPIO4{slash}KBR1-PadP$43)") (class "Default")
      (node (ref "U9") (pin "P$43") (pinfunction "GPIO4/KBR1_P$43") (pintype "bidirectional"))
    )
    (net (code "95") (name "unconnected-(U9-GPIO5{slash}KBR0-PadP$44)") (class "Default")
      (node (ref "U9") (pin "P$44") (pinfunction "GPIO5/KBR0_P$44") (pintype "bidirectional"))
    )
    (net (code "96") (name "unconnected-(U9-GPIO6{slash}KBC4-PadP$47)") (class "Default")
      (node (ref "U9") (pin "P$47") (pinfunction "GPIO6/KBC4_P$47") (pintype "bidirectional"))
    )
    (net (code "97") (name "unconnected-(U9-GPIO7{slash}KBC3-PadP$48)") (class "Default")
      (node (ref "U9") (pin "P$48") (pinfunction "GPIO7/KBC3_P$48") (pintype "bidirectional"))
    )
    (net (code "98") (name "unconnected-(U9-GPIO8{slash}KBC2-PadP$49)") (class "Default")
      (node (ref "U9") (pin "P$49") (pinfunction "GPIO8/KBC2_P$49") (pintype "bidirectional"))
    )
    (net (code "99") (name "unconnected-(U9-GPIO9{slash}KBC1-PadP$50)") (class "Default")
      (node (ref "U9") (pin "P$50") (pinfunction "GPIO9/KBC1_P$50") (pintype "bidirectional"))
    )
    (net (code "100") (name "unconnected-(U9-GPIO10-PadP$51)") (class "Default")
      (node (ref "U9") (pin "P$51") (pinfunction "GPIO10_P$51") (pintype "bidirectional"))
    )
    (net (code "101") (name "unconnected-(U9-GPIO11-PadP$67)") (class "Default")
      (node (ref "U9") (pin "P$67") (pinfunction "GPIO11_P$67") (pintype "bidirectional"))
    )
    (net (code "102") (name "unconnected-(U9-GPIO12-PadP$68)") (class "Default")
      (node (ref "U9") (pin "P$68") (pinfunction "GPIO12_P$68") (pintype "bidirectional"))
    )
    (net (code "103") (name "unconnected-(U9-LINE_L-PadP$24)") (class "Default")
      (node (ref "U9") (pin "P$24") (pinfunction "LINE_L_P$24") (pintype "bidirectional"))
    )
    (net (code "104") (name "unconnected-(U9-LINE_R-PadP$23)") (class "Default")
      (node (ref "U9") (pin "P$23") (pinfunction "LINE_R_P$23") (pintype "bidirectional"))
    )
    (net (code "105") (name "unconnected-(U9-MC_N-PadP$20)") (class "Default")
      (node (ref "U9") (pin "P$20") (pinfunction "MC_N_P$20") (pintype "bidirectional"))
    )
    (net (code "106") (name "unconnected-(U9-MC_P-PadP$19)") (class "Default")
      (node (ref "U9") (pin "P$19") (pinfunction "MC_P_P$19") (pintype "bidirectional"))
    )
    (net (code "107") (name "unconnected-(U9-NC1-PadP$2)") (class "Default")
      (node (ref "U9") (pin "P$2") (pinfunction "NC1_P$2") (pintype "bidirectional"))
    )
    (net (code "108") (name "unconnected-(U9-NC2-PadP$6)") (class "Default")
      (node (ref "U9") (pin "P$6") (pinfunction "NC2_P$6") (pintype "bidirectional"))
    )
    (net (code "109") (name "unconnected-(U9-NRST-PadP$16)") (class "Default")
      (node (ref "U9") (pin "P$16") (pinfunction "NRST_P$16") (pintype "bidirectional"))
    )
    (net (code "110") (name "unconnected-(U9-PWM1-PadP$35)") (class "Default")
      (node (ref "U9") (pin "P$35") (pinfunction "PWM1_P$35") (pintype "bidirectional"))
    )
    (net (code "111") (name "unconnected-(U9-PWM2-PadP$36)") (class "Default")
      (node (ref "U9") (pin "P$36") (pinfunction "PWM2_P$36") (pintype "bidirectional"))
    )
    (net (code "112") (name "unconnected-(U9-RI-PadP$4)") (class "Default")
      (node (ref "U9") (pin "P$4") (pinfunction "RI_P$4") (pintype "bidirectional"))
    )
    (net (code "113") (name "unconnected-(U9-RTS-PadP$8)") (class "Default")
      (node (ref "U9") (pin "P$8") (pinfunction "RTS_P$8") (pintype "bidirectional"))
    )
    (net (code "114") (name "unconnected-(U9-SCL-PadP$38)") (class "Default")
      (node (ref "U9") (pin "P$38") (pinfunction "SCL_P$38") (pintype "bidirectional"))
    )
    (net (code "115") (name "unconnected-(U9-SDA-PadP$37)") (class "Default")
      (node (ref "U9") (pin "P$37") (pinfunction "SDA_P$37") (pintype "bidirectional"))
    )
    (net (code "116") (name "unconnected-(U9-SIM_PRES.-PadP$34)") (class "Default")
      (node (ref "U9") (pin "P$34") (pinfunction "SIM_PRES._P$34") (pintype "bidirectional"))
    )
    (net (code "117") (name "unconnected-(U9-SPK_N-PadP$22)") (class "Default")
      (node (ref "U9") (pin "P$22") (pinfunction "SPK_N_P$22") (pintype "bidirectional"))
    )
    (net (code "118") (name "unconnected-(U9-SPK_P-PadP$21)") (class "Default")
      (node (ref "U9") (pin "P$21") (pinfunction "SPK_P_P$21") (pintype "bidirectional"))
    )
    (net (code "119") (name "unconnected-(U9-STATUS-PadP$66)") (class "Default")
      (node (ref "U9") (pin "P$66") (pinfunction "STATUS_P$66") (pintype "bidirectional"))
    )
    (net (code "120") (name "unconnected-(U9-VDD_EXT-PadP$15)") (class "Default")
      (node (ref "U9") (pin "P$15") (pinfunction "VDD_EXT_P$15") (pintype "bidirectional"))
    )
    (net (code "121") (name "unconnected-(U9-VRTC-PadP$26)") (class "Default")
      (node (ref "U9") (pin "P$26") (pinfunction "VRTC_P$26") (pintype "bidirectional"))
    )
    (net (code "122") (name "unconnected-(U10-VPP-PadC6)") (class "Default")
      (node (ref "U10") (pin "C6") (pinfunction "VPP_C6") (pintype "bidirectional"))
    )
    (net (code "123") (name "unconnected-(U12-Pad3)") (class "Default")
      (node (ref "U12") (pin "3") (pinfunction "3_3") (pintype "bidirectional"))
    )
  )
)
